# Sheet1.net
KiCad netlist of a schematic drawn in Altium Designer
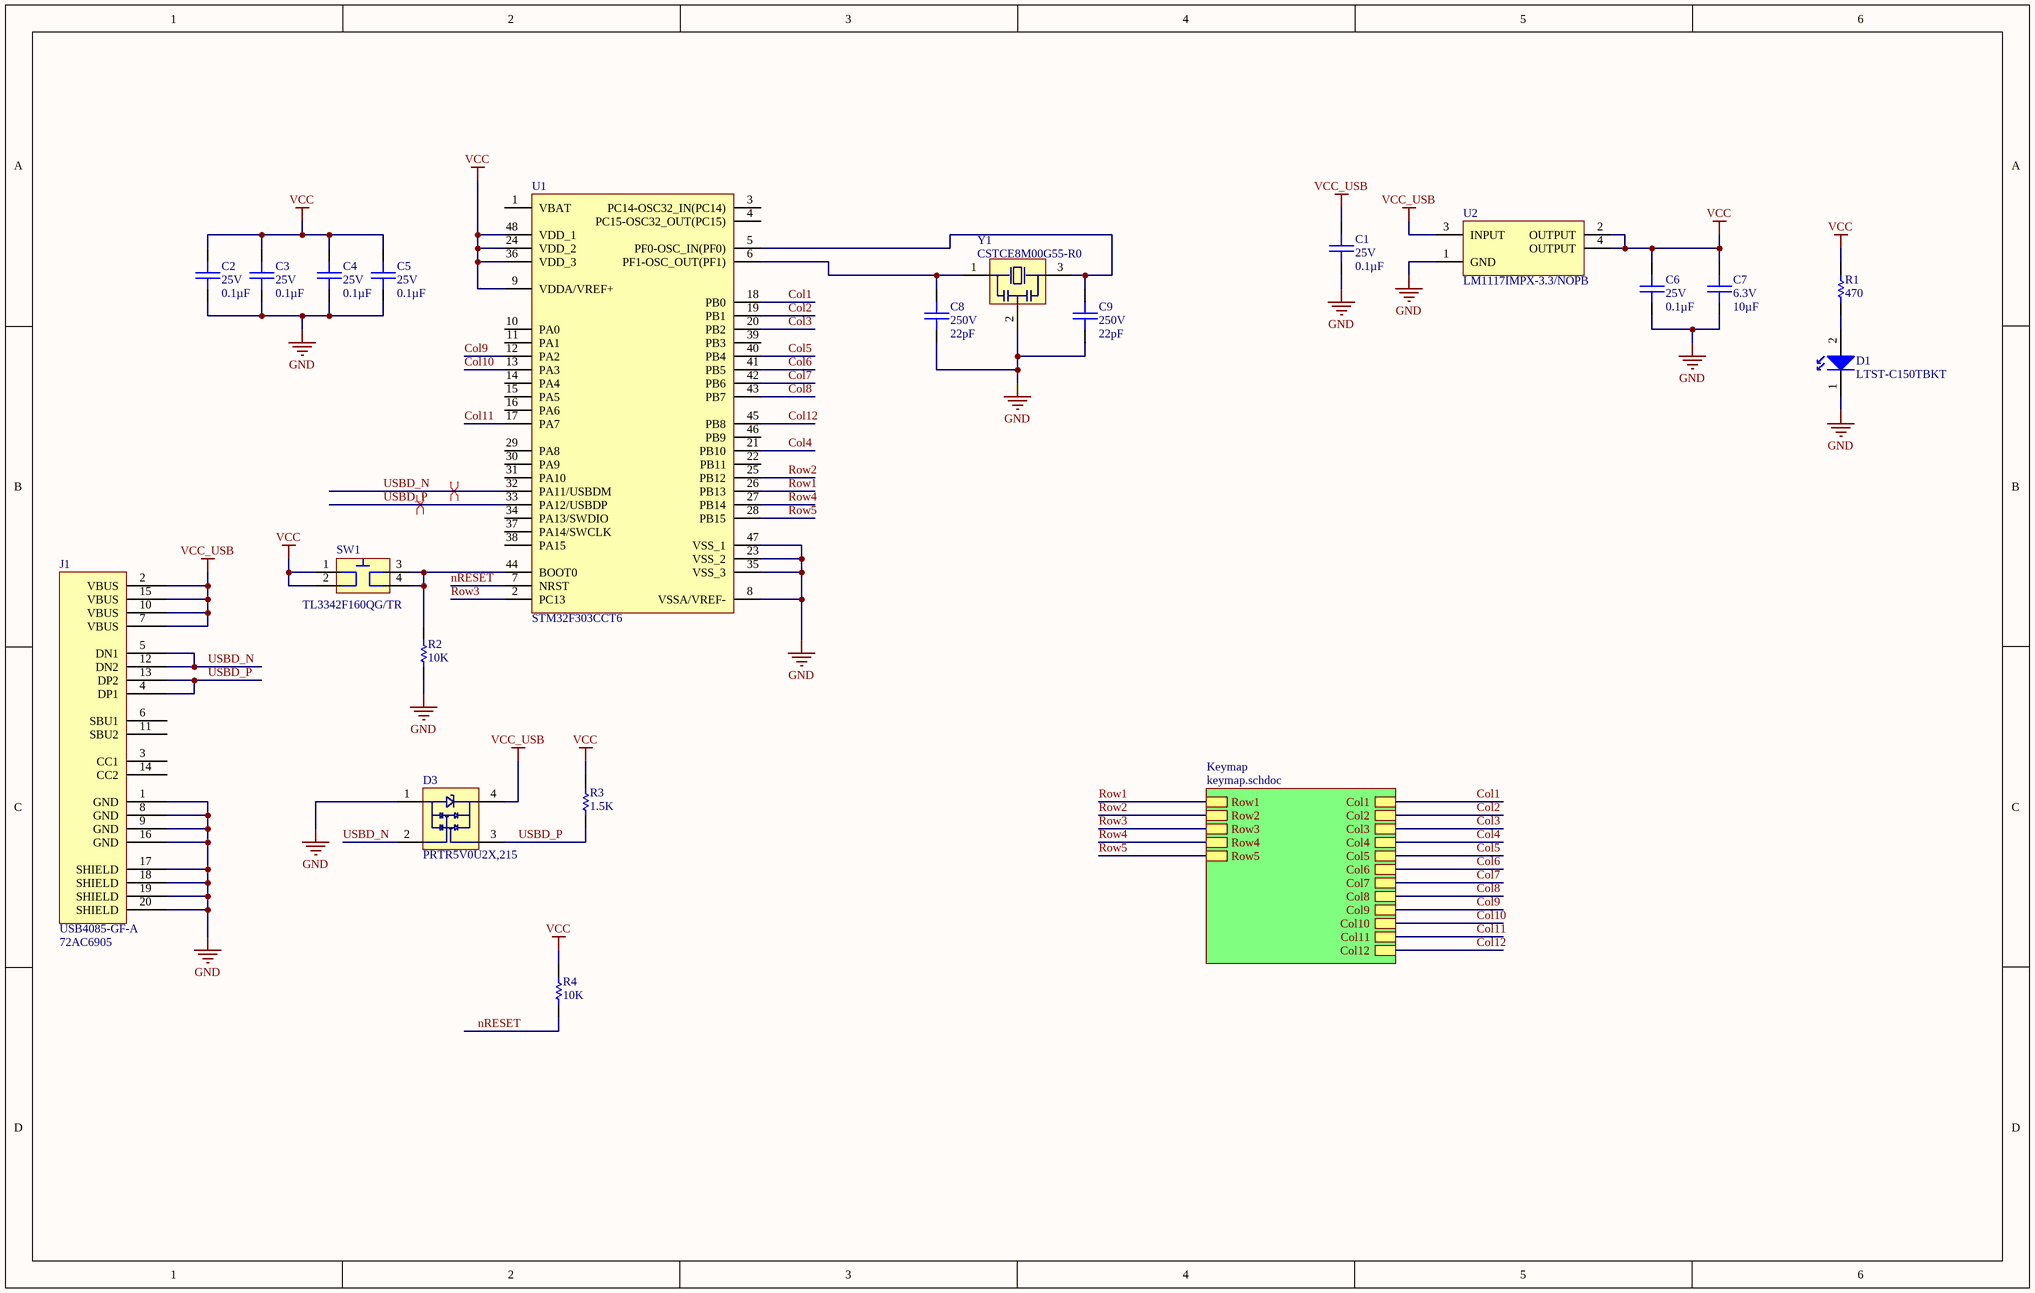
[diagram p0: Sheet1.SchDoc]

(export (version "E")
  (design (tool "Eeschema 10.0.6"))
  (components
    (comp (ref "C1")
      (value "0.1µF")
      (footprint "CAPC_0603(1.6X0.8)_N")
      (description "Generic Capacitor")
      (fields
        (field (name "TOLERANCE") "±10%")
        (field (name "VOLTAGE") "25V")
        (field (name "MANUFACTURER") "Generic")
      )
      (libsource (lib "Safari") (part "CAPC"))
    )
    (comp (ref "C2")
      (value "0.1µF")
      (footprint "CAPC_0603(1.6X0.8)_N")
      (description "Generic Capacitor")
      (fields
        (field (name "TOLERANCE") "±10%")
        (field (name "VOLTAGE") "25V")
        (field (name "MANUFACTURER") "Generic")
      )
      (libsource (lib "Safari") (part "CAPC"))
    )
    (comp (ref "C3")
      (value "0.1µF")
      (footprint "CAPC_0603(1.6X0.8)_N")
      (description "Generic Capacitor")
      (fields
        (field (name "TOLERANCE") "±10%")
        (field (name "VOLTAGE") "25V")
        (field (name "MANUFACTURER") "Generic")
      )
      (libsource (lib "Safari") (part "CAPC"))
    )
    (comp (ref "C4")
      (value "0.1µF")
      (footprint "CAPC_0603(1.6X0.8)_N")
      (description "Generic Capacitor")
      (fields
        (field (name "TOLERANCE") "±10%")
        (field (name "VOLTAGE") "25V")
        (field (name "MANUFACTURER") "Generic")
      )
      (libsource (lib "Safari") (part "CAPC"))
    )
    (comp (ref "C5")
      (value "0.1µF")
      (footprint "CAPC_0603(1.6X0.8)_N")
      (description "Generic Capacitor")
      (fields
        (field (name "TOLERANCE") "±10%")
        (field (name "VOLTAGE") "25V")
        (field (name "MANUFACTURER") "Generic")
      )
      (libsource (lib "Safari") (part "CAPC"))
    )
    (comp (ref "C6")
      (value "0.1µF")
      (footprint "CAPC_0603(1.6X0.8)_N")
      (description "Generic Capacitor")
      (fields
        (field (name "TOLERANCE") "±10%")
        (field (name "VOLTAGE") "25V")
        (field (name "MANUFACTURER") "Generic")
      )
      (libsource (lib "Safari") (part "CAPC"))
    )
    (comp (ref "C7")
      (value "10µF")
      (footprint "CAPC_0603(1.6X0.8)_N")
      (description "Generic Capacitor")
      (fields
        (field (name "TOLERANCE") "±20%")
        (field (name "VOLTAGE") "6.3V")
        (field (name "MANUFACTURER") "Generic")
      )
      (libsource (lib "Safari") (part "CAPC"))
    )
    (comp (ref "C8")
      (value "22pF")
      (footprint "CAPC_0603(1.6X0.8)_N")
      (description "Generic Capacitor")
      (fields
        (field (name "TOLERANCE") "±2%")
        (field (name "VOLTAGE") "250V")
        (field (name "MANUFACTURER") "Generic")
      )
      (libsource (lib "Safari") (part "CAPC"))
    )
    (comp (ref "C9")
      (value "22pF")
      (footprint "CAPC_0603(1.6X0.8)_N")
      (description "Generic Capacitor")
      (fields
        (field (name "TOLERANCE") "±2%")
        (field (name "VOLTAGE") "250V")
        (field (name "MANUFACTURER") "Generic")
      )
      (libsource (lib "Safari") (part "CAPC"))
    )
    (comp (ref "D1")
      (value "LED 468NM BLUE CLEAR 1206 SMD")
      (footprint "LTST-C150TBKT_N")
      (fields
        (field (name "MANUFACTURER") "Lite-On Inc")
        (field (name "MANUFACTURER PART NUMBER") "LTST-C150TBKT")
        (field (name "SAFARIPARTNUMBER") "15 25012RC")
      )
      (libsource (lib "Safari") (part "LTST-C150TBKT"))
    )
    (comp (ref "D3")
      (value "TVS DIODE 5.5VWM SOT143B")
      (footprint "NXP_SOT143B_N")
      (fields
        (field (name "MANUFACTURER") "NXP Semiconductors")
        (field (name "MANUFACTURER PART NUMBER") "PRTR5V0U2X,215")
        (field (name "SAFARIPARTNUMBER") "15 27314RC")
      )
      (libsource (lib "Safari") (part "PRTR5V0U2X,215"))
    )
    (comp (ref "J1")
      (value "USB4085-GF-A")
      (footprint "GCT_USB4085-GF-A_MN")
      (description "USB4085 Series 20 V PCB Top Mount USB 2.0 Type C Receptacle")
      (fields (field (name "SUPPLIER PART NUMBER 1") "72AC6905"))
      (libsource (lib "USB4085-GF-A") (part "USB4085-GF-A"))
    )
    (comp (ref "R1")
      (value "470")
      (footprint "RESC_0603(1.6X0.8)_N")
      (description "Generic Resistor")
      (fields (field (name "TOLERANCE") "5%") (field (name "POWER") "0.1W"))
      (libsource (lib "Safari") (part "RES"))
    )
    (comp (ref "R2")
      (value "10K")
      (footprint "RESC_0603(1.6X0.8)_N")
      (description "Generic Resistor")
      (fields (field (name "TOLERANCE") "5%") (field (name "POWER") "0.1W"))
      (libsource (lib "Safari") (part "RES"))
    )
    (comp (ref "R3")
      (value "1.5K")
      (footprint "RESC_0603(1.6X0.8)_N")
      (description "Generic Resistor")
      (fields (field (name "TOLERANCE") "5%") (field (name "POWER") "0.1W"))
      (libsource (lib "Safari") (part "RES"))
    )
    (comp (ref "R4")
      (value "10K")
      (footprint "RESC_0603(1.6X0.8)_N")
      (description "Generic Resistor")
      (fields (field (name "TOLERANCE") "5%") (field (name "POWER") "0.1W"))
      (libsource (lib "Safari") (part "RES"))
    )
    (comp (ref "SW1")
      (value "SWITCH TACTILE SPST-NO 0.05A 12V")
      (footprint "TL3342F160QG-TR")
      (fields
        (field (name "MANUFACTURER") "E-Switch")
        (field (name "MANUFACTURER PART NUMBER") "TL3342F160QG/TR")
      )
      (libsource (lib "Safari") (part "TL3342F160QG-TR"))
    )
    (comp (ref "U1")
      (value "32BIT, CORTEX-M4, 72MHZ, LQFP-48")
      (footprint "ST_LQFP-48-7x7x1.4_MN")
      (fields
        (field (name "MANUFACTURER PART NUMBER 1") "STM32F303CCT6")
        (field (name "MANUFACTURER PART NUMBER") "STM32F303CCT6")
        (field (name "MANUFACTURER") "ST Micro")
      )
      (libsource (lib "Safari") (part "STM32F303CCT6"))
    )
    (comp (ref "U2")
      (value "IC REG LDO 3.3V 0.8A SOT223")
      (footprint "TI_DCY-R-PDSO-G4_N")
      (fields
        (field (name "MANUFACTURER") "Texas Instruments")
        (field (name "MANUFACTURER PART NUMBER") "LM1117IMPX-3.3/NOPB")
        (field (name "SAFARIPARTNUMBER") "15 24656RC")
      )
      (libsource (lib "Safari") (part "LM1117IMPX-3.3-NOPB"))
    )
    (comp (ref "Y1")
      (value "CER RESONATOR 8.00MHZ SMD")
      (footprint "CSTCE8M00G55-R0")
      (fields
        (field (name "MANUFACTURER") "Murata Electronics North America")
        (field (name "MANUFACTURER PART NUMBER") "CSTCE8M00G55-R0")
      )
      (libsource (lib "Safari") (part "CSTCE8M00G55-R0"))
    )
  )
  (nets
    (net (code "1") (name "/Col1") (class "Default")
      (node (ref "U1") (pin "18") (pinfunction "PB0_18") (pintype "passive"))
    )
    (net (code "2") (name "/Col2") (class "Default")
      (node (ref "U1") (pin "19") (pinfunction "PB1_19") (pintype "passive"))
    )
    (net (code "3") (name "/Col3") (class "Default")
      (node (ref "U1") (pin "20") (pinfunction "PB2_20") (pintype "passive"))
    )
    (net (code "4") (name "/Col4") (class "Default")
      (node (ref "U1") (pin "21") (pinfunction "PB10_21") (pintype "passive"))
    )
    (net (code "5") (name "/Col5") (class "Default")
      (node (ref "U1") (pin "40") (pinfunction "PB4_40") (pintype "passive"))
    )
    (net (code "6") (name "/Col6") (class "Default")
      (node (ref "U1") (pin "41") (pinfunction "PB5_41") (pintype "passive"))
    )
    (net (code "7") (name "/Col7") (class "Default")
      (node (ref "U1") (pin "42") (pinfunction "PB6_42") (pintype "passive"))
    )
    (net (code "8") (name "/Col8") (class "Default")
      (node (ref "U1") (pin "43") (pinfunction "PB7_43") (pintype "passive"))
    )
    (net (code "9") (name "/Col9") (class "Default")
      (node (ref "U1") (pin "12") (pinfunction "PA2_12") (pintype "passive"))
    )
    (net (code "10") (name "/Col10") (class "Default")
      (node (ref "U1") (pin "13") (pinfunction "PA3_13") (pintype "passive"))
    )
    (net (code "11") (name "/Col11") (class "Default")
      (node (ref "U1") (pin "17") (pinfunction "PA7_17") (pintype "passive"))
    )
    (net (code "12") (name "/Col12") (class "Default")
      (node (ref "U1") (pin "45") (pinfunction "PB8_45") (pintype "passive"))
    )
    (net (code "13") (name "/Row1") (class "Default")
      (node (ref "U1") (pin "26") (pinfunction "PB13_26") (pintype "passive"))
    )
    (net (code "14") (name "/Row2") (class "Default")
      (node (ref "U1") (pin "25") (pinfunction "PB12_25") (pintype "passive"))
    )
    (net (code "15") (name "/Row3") (class "Default")
      (node (ref "U1") (pin "2") (pinfunction "PC13_2") (pintype "passive"))
    )
    (net (code "16") (name "/Row4") (class "Default")
      (node (ref "U1") (pin "27") (pinfunction "PB14_27") (pintype "passive"))
    )
    (net (code "17") (name "/Row5") (class "Default")
      (node (ref "U1") (pin "28") (pinfunction "PB15_28") (pintype "passive"))
    )
    (net (code "18") (name "/USBD_N") (class "Default")
      (node (ref "D3") (pin "2") (pinfunction "IO1_2") (pintype "passive"))
      (node (ref "J1") (pin "12") (pinfunction "DN2_12") (pintype "passive"))
      (node (ref "J1") (pin "5") (pinfunction "DN1_5") (pintype "passive"))
      (node (ref "U1") (pin "32") (pinfunction "PA11/USBDM_32") (pintype "passive"))
    )
    (net (code "19") (name "/USBD_P") (class "Default")
      (node (ref "D3") (pin "3") (pinfunction "IO2_3") (pintype "passive"))
      (node (ref "J1") (pin "13") (pinfunction "DP2_13") (pintype "passive"))
      (node (ref "J1") (pin "4") (pinfunction "DP1_4") (pintype "passive"))
      (node (ref "R3") (pin "1") (pinfunction "1_1") (pintype "passive"))
      (node (ref "U1") (pin "33") (pinfunction "PA12/USBDP_33") (pintype "passive"))
    )
    (net (code "20") (name "/nRESET") (class "Default")
      (node (ref "R4") (pin "1") (pinfunction "1_1") (pintype "passive"))
      (node (ref "U1") (pin "7") (pinfunction "NRST_7") (pintype "passive"))
    )
    (net (code "21") (name "GND") (class "Default")
      (node (ref "C1") (pin "2") (pinfunction "2_2") (pintype "passive"))
      (node (ref "C2") (pin "2") (pinfunction "2_2") (pintype "passive"))
      (node (ref "C3") (pin "2") (pinfunction "2_2") (pintype "passive"))
      (node (ref "C4") (pin "2") (pinfunction "2_2") (pintype "passive"))
      (node (ref "C5") (pin "2") (pinfunction "2_2") (pintype "passive"))
      (node (ref "C6") (pin "2") (pinfunction "2_2") (pintype "passive"))
      (node (ref "C7") (pin "2") (pinfunction "2_2") (pintype "passive"))
      (node (ref "C8") (pin "2") (pinfunction "2_2") (pintype "passive"))
      (node (ref "C9") (pin "2") (pinfunction "2_2") (pintype "passive"))
      (node (ref "D1") (pin "1") (pinfunction "K_1") (pintype "passive"))
      (node (ref "D3") (pin "1") (pinfunction "GND_1") (pintype "passive"))
      (node (ref "J1") (pin "1") (pinfunction "GND_1") (pintype "passive"))
      (node (ref "J1") (pin "16") (pinfunction "GND_16") (pintype "passive"))
      (node (ref "J1") (pin "17") (pinfunction "SHIELD_17") (pintype "passive"))
      (node (ref "J1") (pin "18") (pinfunction "SHIELD_18") (pintype "passive"))
      (node (ref "J1") (pin "19") (pinfunction "SHIELD_19") (pintype "passive"))
      (node (ref "J1") (pin "20") (pinfunction "SHIELD_20") (pintype "passive"))
      (node (ref "J1") (pin "8") (pinfunction "GND_8") (pintype "passive"))
      (node (ref "J1") (pin "9") (pinfunction "GND_9") (pintype "passive"))
      (node (ref "R2") (pin "1") (pinfunction "1_1") (pintype "passive"))
      (node (ref "U1") (pin "23") (pinfunction "VSS_2_23") (pintype "passive"))
      (node (ref "U1") (pin "35") (pinfunction "VSS_3_35") (pintype "passive"))
      (node (ref "U1") (pin "47") (pinfunction "VSS_1_47") (pintype "passive"))
      (node (ref "U1") (pin "8") (pinfunction "VSSA/VREF-_8") (pintype "passive"))
      (node (ref "U2") (pin "1") (pinfunction "GND_1") (pintype "passive"))
      (node (ref "Y1") (pin "2") (pinfunction "2_2") (pintype "passive"))
    )
    (net (code "22") (name "Net-(D1-A)") (class "Default")
      (node (ref "D1") (pin "2") (pinfunction "A_2") (pintype "passive"))
      (node (ref "R1") (pin "1") (pinfunction "1_1") (pintype "passive"))
    )
    (net (code "23") (name "Net-(U1-BOOT0)") (class "Default")
      (node (ref "R2") (pin "2") (pinfunction "2_2") (pintype "passive"))
      (node (ref "SW1") (pin "3") (pinfunction "3_3") (pintype "passive"))
      (node (ref "SW1") (pin "4") (pinfunction "4_4") (pintype "passive"))
      (node (ref "U1") (pin "44") (pinfunction "BOOT0_44") (pintype "passive"))
    )
    (net (code "24") (name "Net-(U1-PF0-OSC_IN(PF0))") (class "Default")
      (node (ref "C9") (pin "1") (pinfunction "1_1") (pintype "passive"))
      (node (ref "U1") (pin "5") (pinfunction "PF0-OSC_IN(PF0)_5") (pintype "passive"))
      (node (ref "Y1") (pin "3") (pinfunction "3_3") (pintype "passive"))
    )
    (net (code "25") (name "Net-(U1-PF1-OSC_OUT(PF1))") (class "Default")
      (node (ref "C8") (pin "1") (pinfunction "1_1") (pintype "passive"))
      (node (ref "U1") (pin "6") (pinfunction "PF1-OSC_OUT(PF1)_6") (pintype "passive"))
      (node (ref "Y1") (pin "1") (pinfunction "1_1") (pintype "passive"))
    )
    (net (code "26") (name "VCC") (class "Default")
      (node (ref "C2") (pin "1") (pinfunction "1_1") (pintype "passive"))
      (node (ref "C3") (pin "1") (pinfunction "1_1") (pintype "passive"))
      (node (ref "C4") (pin "1") (pinfunction "1_1") (pintype "passive"))
      (node (ref "C5") (pin "1") (pinfunction "1_1") (pintype "passive"))
      (node (ref "C6") (pin "1") (pinfunction "1_1") (pintype "passive"))
      (node (ref "C7") (pin "1") (pinfunction "1_1") (pintype "passive"))
      (node (ref "R1") (pin "2") (pinfunction "2_2") (pintype "passive"))
      (node (ref "R3") (pin "2") (pinfunction "2_2") (pintype "passive"))
      (node (ref "R4") (pin "2") (pinfunction "2_2") (pintype "passive"))
      (node (ref "SW1") (pin "1") (pinfunction "1_1") (pintype "passive"))
      (node (ref "SW1") (pin "2") (pinfunction "2_2") (pintype "passive"))
      (node (ref "U1") (pin "24") (pinfunction "VDD_2_24") (pintype "passive"))
      (node (ref "U1") (pin "36") (pinfunction "VDD_3_36") (pintype "passive"))
      (node (ref "U1") (pin "48") (pinfunction "VDD_1_48") (pintype "passive"))
      (node (ref "U1") (pin "9") (pinfunction "VDDA/VREF+_9") (pintype "passive"))
      (node (ref "U2") (pin "2") (pinfunction "OUTPUT_2") (pintype "passive"))
      (node (ref "U2") (pin "4") (pinfunction "OUTPUT_4") (pintype "passive"))
    )
    (net (code "27") (name "VCC_USB") (class "Default")
      (node (ref "C1") (pin "1") (pinfunction "1_1") (pintype "passive"))
      (node (ref "D3") (pin "4") (pinfunction "VCC_4") (pintype "passive"))
      (node (ref "J1") (pin "10") (pinfunction "VBUS_10") (pintype "passive"))
      (node (ref "J1") (pin "15") (pinfunction "VBUS_15") (pintype "passive"))
      (node (ref "J1") (pin "2") (pinfunction "VBUS_2") (pintype "passive"))
      (node (ref "J1") (pin "7") (pinfunction "VBUS_7") (pintype "passive"))
      (node (ref "U2") (pin "3") (pinfunction "INPUT_3") (pintype "passive"))
    )
    (net (code "28") (name "unconnected-(J1-CC1-Pad3)") (class "Default")
      (node (ref "J1") (pin "3") (pinfunction "CC1_3") (pintype "passive"))
    )
    (net (code "29") (name "unconnected-(J1-CC2-Pad14)") (class "Default")
      (node (ref "J1") (pin "14") (pinfunction "CC2_14") (pintype "passive"))
    )
    (net (code "30") (name "unconnected-(J1-SBU1-Pad6)") (class "Default")
      (node (ref "J1") (pin "6") (pinfunction "SBU1_6") (pintype "passive"))
    )
    (net (code "31") (name "unconnected-(J1-SBU2-Pad11)") (class "Default")
      (node (ref "J1") (pin "11") (pinfunction "SBU2_11") (pintype "passive"))
    )
    (net (code "32") (name "unconnected-(U1-PA0-Pad10)") (class "Default")
      (node (ref "U1") (pin "10") (pinfunction "PA0_10") (pintype "passive"))
    )
    (net (code "33") (name "unconnected-(U1-PA1-Pad11)") (class "Default")
      (node (ref "U1") (pin "11") (pinfunction "PA1_11") (pintype "passive"))
    )
    (net (code "34") (name "unconnected-(U1-PA4-Pad14)") (class "Default")
      (node (ref "U1") (pin "14") (pinfunction "PA4_14") (pintype "passive"))
    )
    (net (code "35") (name "unconnected-(U1-PA5-Pad15)") (class "Default")
      (node (ref "U1") (pin "15") (pinfunction "PA5_15") (pintype "passive"))
    )
    (net (code "36") (name "unconnected-(U1-PA6-Pad16)") (class "Default")
      (node (ref "U1") (pin "16") (pinfunction "PA6_16") (pintype "passive"))
    )
    (net (code "37") (name "unconnected-(U1-PA8-Pad29)") (class "Default")
      (node (ref "U1") (pin "29") (pinfunction "PA8_29") (pintype "passive"))
    )
    (net (code "38") (name "unconnected-(U1-PA9-Pad30)") (class "Default")
      (node (ref "U1") (pin "30") (pinfunction "PA9_30") (pintype "passive"))
    )
    (net (code "39") (name "unconnected-(U1-PA10-Pad31)") (class "Default")
      (node (ref "U1") (pin "31") (pinfunction "PA10_31") (pintype "passive"))
    )
    (net (code "40") (name "unconnected-(U1-PA13{slash}SWDIO-Pad34)") (class "Default")
      (node (ref "U1") (pin "34") (pinfunction "PA13/SWDIO_34") (pintype "passive"))
    )
    (net (code "41") (name "unconnected-(U1-PA14{slash}SWCLK-Pad37)") (class "Default")
      (node (ref "U1") (pin "37") (pinfunction "PA14/SWCLK_37") (pintype "passive"))
    )
    (net (code "42") (name "unconnected-(U1-PA15-Pad38)") (class "Default")
      (node (ref "U1") (pin "38") (pinfunction "PA15_38") (pintype "passive"))
    )
    (net (code "43") (name "unconnected-(U1-PB3-Pad39)") (class "Default")
      (node (ref "U1") (pin "39") (pinfunction "PB3_39") (pintype "passive"))
    )
    (net (code "44") (name "unconnected-(U1-PB9-Pad46)") (class "Default")
      (node (ref "U1") (pin "46") (pinfunction "PB9_46") (pintype "passive"))
    )
    (net (code "45") (name "unconnected-(U1-PB11-Pad22)") (class "Default")
      (node (ref "U1") (pin "22") (pinfunction "PB11_22") (pintype "passive"))
    )
    (net (code "46") (name "unconnected-(U1-PC14-OSC32_IN(PC14)-Pad3)") (class "Default")
      (node (ref "U1") (pin "3") (pinfunction "PC14-OSC32_IN(PC14)_3") (pintype "passive"))
    )
    (net (code "47") (name "unconnected-(U1-PC15-OSC32_OUT(PC15)-Pad4)") (class "Default")
      (node (ref "U1") (pin "4") (pinfunction "PC15-OSC32_OUT(PC15)_4") (pintype "passive"))
    )
    (net (code "48") (name "unconnected-(U1-VBAT-Pad1)") (class "Default")
      (node (ref "U1") (pin "1") (pinfunction "VBAT_1") (pintype "passive"))
    )
  )
)
